# ScreenbreakOut.net
KiCad netlist of a schematic drawn in EAGLE
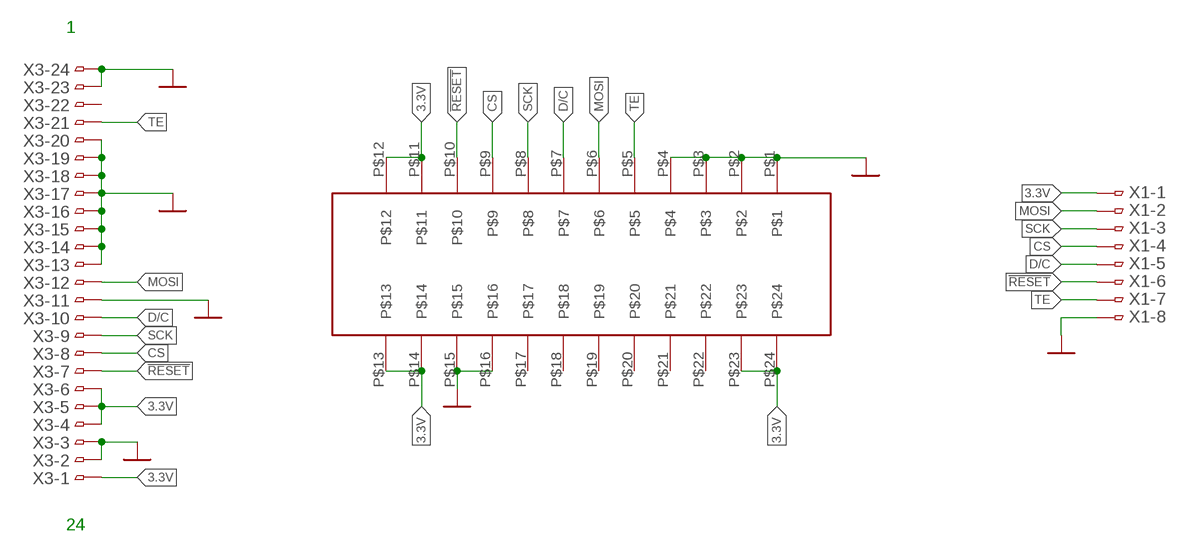
[diagram p0: schematic, sheet 1]

(export (version "E")
  (design (tool "Eeschema 10.0.6"))
  (components
    (comp (ref "U$1")
      (value "CICULARSCREENRELATED_OK-14F24-04")
      (footprint "eagle-import:CICULARSCREENRELATED_OK-14F24-04")
      (libsource (lib "eagle-import") (part "CICULARSCREENRELATED_OK-14F24-04"))
    )
    (comp (ref "X1")
      (value "SCREENBREAKOUT_LEDMATRIXFPCCONNECTOR_CON-HIROSE_FH12-08S-1SH")
      (footprint "eagle-import:SCREENBREAKOUT_LEDMATRIXFPCCONNECTOR_CON-HIROSE_FH12-08S-1SH")
      (libsource (lib "eagle-import") (part "SCREENBREAKOUT_LEDMATRIXFPCCONNECTOR_CON-HIROSE_FH12-08S-1SH"))
    )
    (comp (ref "X3")
      (value "CON-HIROSE_FH12-24S-0.5SH")
      (footprint "eagle-import:CON-HIROSE_FH12-24S-0.5SH")
      (fields (field (name "MPN") "FH12-24S-0.5SH(55)"))
      (libsource (lib "eagle-import") (part "CON-HIROSE_FH12-24S-0.5SH"))
    )
  )
  (nets
    (net (code "1") (name "/~{RESET}") (class "Default")
      (node (ref "U$1") (pin "P$10") (pinfunction "P$10_P$10") (pintype "bidirectional"))
      (node (ref "X1") (pin "6") (pinfunction "1_6") (pintype "passive"))
      (node (ref "X3") (pin "7") (pinfunction "1_7") (pintype "passive"))
    )
    (net (code "2") (name "3.3V") (class "Default")
      (node (ref "U$1") (pin "P$11") (pinfunction "P$11_P$11") (pintype "bidirectional"))
      (node (ref "U$1") (pin "P$12") (pinfunction "P$12_P$12") (pintype "bidirectional"))
      (node (ref "U$1") (pin "P$13") (pinfunction "P$13_P$13") (pintype "bidirectional"))
      (node (ref "U$1") (pin "P$14") (pinfunction "P$14_P$14") (pintype "bidirectional"))
      (node (ref "U$1") (pin "P$23") (pinfunction "P$23_P$23") (pintype "bidirectional"))
      (node (ref "U$1") (pin "P$24") (pinfunction "P$24_P$24") (pintype "bidirectional"))
      (node (ref "X1") (pin "1") (pinfunction "1_1") (pintype "passive"))
      (node (ref "X3") (pin "1") (pinfunction "1_1") (pintype "passive"))
      (node (ref "X3") (pin "4") (pinfunction "1_4") (pintype "passive"))
      (node (ref "X3") (pin "5") (pinfunction "1_5") (pintype "passive"))
      (node (ref "X3") (pin "6") (pinfunction "1_6") (pintype "passive"))
    )
    (net (code "3") (name "CS") (class "Default")
      (node (ref "U$1") (pin "P$9") (pinfunction "P$9_P$9") (pintype "bidirectional"))
      (node (ref "X1") (pin "4") (pinfunction "1_4") (pintype "passive"))
      (node (ref "X3") (pin "8") (pinfunction "1_8") (pintype "passive"))
    )
    (net (code "4") (name "D{slash}C") (class "Default")
      (node (ref "U$1") (pin "P$7") (pinfunction "P$7_P$7") (pintype "bidirectional"))
      (node (ref "X1") (pin "5") (pinfunction "1_5") (pintype "passive"))
      (node (ref "X3") (pin "10") (pinfunction "1_10") (pintype "passive"))
    )
    (net (code "5") (name "MOSI") (class "Default")
      (node (ref "U$1") (pin "P$6") (pinfunction "P$6_P$6") (pintype "bidirectional"))
      (node (ref "X1") (pin "2") (pinfunction "1_2") (pintype "passive"))
      (node (ref "X3") (pin "12") (pinfunction "1_12") (pintype "passive"))
    )
    (net (code "6") (name "SCK") (class "Default")
      (node (ref "U$1") (pin "P$8") (pinfunction "P$8_P$8") (pintype "bidirectional"))
      (node (ref "X1") (pin "3") (pinfunction "1_3") (pintype "passive"))
      (node (ref "X3") (pin "9") (pinfunction "1_9") (pintype "passive"))
    )
    (net (code "7") (name "SCREENBREAKOUT_3-5-PIN-SMD_GND") (class "Default")
      (node (ref "U$1") (pin "P$1") (pinfunction "P$1_P$1") (pintype "bidirectional"))
      (node (ref "U$1") (pin "P$15") (pinfunction "P$15_P$15") (pintype "bidirectional"))
      (node (ref "U$1") (pin "P$16") (pinfunction "P$16_P$16") (pintype "bidirectional"))
      (node (ref "U$1") (pin "P$2") (pinfunction "P$2_P$2") (pintype "bidirectional"))
      (node (ref "U$1") (pin "P$3") (pinfunction "P$3_P$3") (pintype "bidirectional"))
      (node (ref "U$1") (pin "P$4") (pinfunction "P$4_P$4") (pintype "bidirectional"))
      (node (ref "X1") (pin "8") (pinfunction "1_8") (pintype "passive"))
      (node (ref "X3") (pin "11") (pinfunction "1_11") (pintype "passive"))
      (node (ref "X3") (pin "13") (pinfunction "1_13") (pintype "passive"))
      (node (ref "X3") (pin "14") (pinfunction "1_14") (pintype "passive"))
      (node (ref "X3") (pin "15") (pinfunction "1_15") (pintype "passive"))
      (node (ref "X3") (pin "16") (pinfunction "1_16") (pintype "passive"))
      (node (ref "X3") (pin "17") (pinfunction "1_17") (pintype "passive"))
      (node (ref "X3") (pin "18") (pinfunction "1_18") (pintype "passive"))
      (node (ref "X3") (pin "19") (pinfunction "1_19") (pintype "passive"))
      (node (ref "X3") (pin "2") (pinfunction "1_2") (pintype "passive"))
      (node (ref "X3") (pin "20") (pinfunction "1_20") (pintype "passive"))
      (node (ref "X3") (pin "23") (pinfunction "1_23") (pintype "passive"))
      (node (ref "X3") (pin "24") (pinfunction "1_24") (pintype "passive"))
      (node (ref "X3") (pin "3") (pinfunction "1_3") (pintype "passive"))
    )
    (net (code "8") (name "TE") (class "Default")
      (node (ref "U$1") (pin "P$5") (pinfunction "P$5_P$5") (pintype "bidirectional"))
      (node (ref "X1") (pin "7") (pinfunction "1_7") (pintype "passive"))
      (node (ref "X3") (pin "21") (pinfunction "1_21") (pintype "passive"))
    )
    (net (code "9") (name "unconnected-(U$1-PadP$17)") (class "Default")
      (node (ref "U$1") (pin "P$17") (pinfunction "P$17_P$17") (pintype "bidirectional"))
    )
    (net (code "10") (name "unconnected-(U$1-PadP$18)") (class "Default")
      (node (ref "U$1") (pin "P$18") (pinfunction "P$18_P$18") (pintype "bidirectional"))
    )
    (net (code "11") (name "unconnected-(U$1-PadP$19)") (class "Default")
      (node (ref "U$1") (pin "P$19") (pinfunction "P$19_P$19") (pintype "bidirectional"))
    )
    (net (code "12") (name "unconnected-(U$1-PadP$20)") (class "Default")
      (node (ref "U$1") (pin "P$20") (pinfunction "P$20_P$20") (pintype "bidirectional"))
    )
    (net (code "13") (name "unconnected-(U$1-PadP$21)") (class "Default")
      (node (ref "U$1") (pin "P$21") (pinfunction "P$21_P$21") (pintype "bidirectional"))
    )
    (net (code "14") (name "unconnected-(U$1-PadP$22)") (class "Default")
      (node (ref "U$1") (pin "P$22") (pinfunction "P$22_P$22") (pintype "bidirectional"))
    )
    (net (code "15") (name "unconnected-(X3O-1-Pad22)") (class "Default")
      (node (ref "X3") (pin "22") (pinfunction "1_22") (pintype "passive"))
    )
  )
)
